# LightBox_Schematic_Updated_11-27.net
KiCad netlist of a schematic drawn in EAGLE
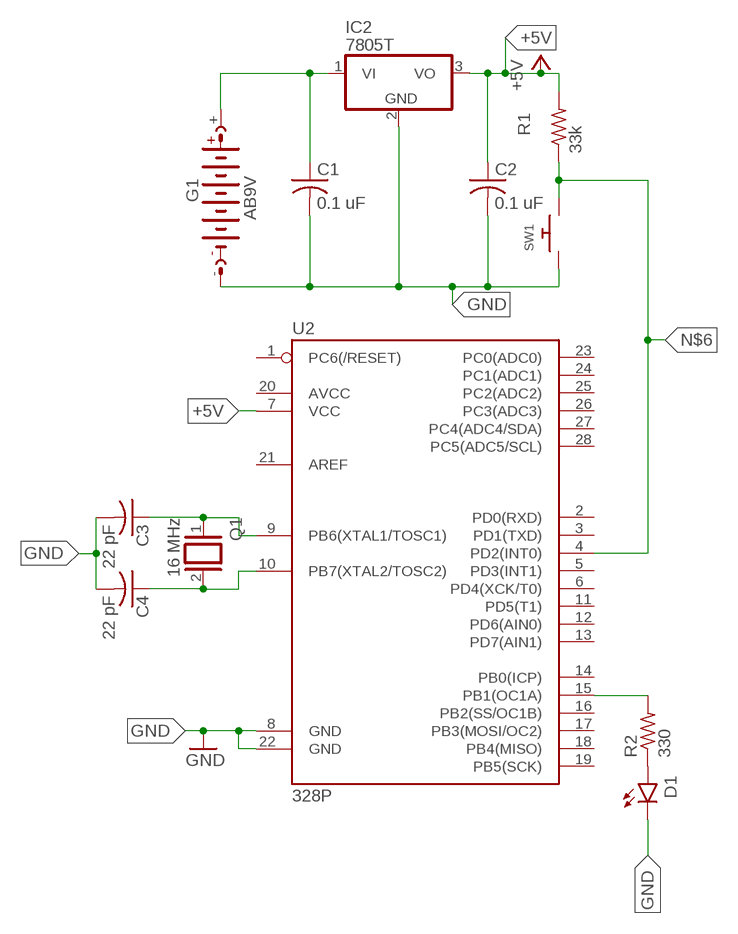
[diagram p0: schematic, sheet 1]

(export (version "E")
  (design (tool "Eeschema 10.0.6"))
  (components
    (comp (ref "C1")
      (value "0.1 uF")
      (footprint "eagle-import:C0805")
      (libsource (lib "eagle-import") (part "C-USC0805"))
    )
    (comp (ref "C2")
      (value "0.1 uF")
      (footprint "eagle-import:C0805")
      (libsource (lib "eagle-import") (part "C-USC0805"))
    )
    (comp (ref "C3")
      (value "22 pF")
      (footprint "eagle-import:C0805")
      (libsource (lib "eagle-import") (part "C-USC0805"))
    )
    (comp (ref "C4")
      (value "22 pF")
      (footprint "eagle-import:C0805")
      (libsource (lib "eagle-import") (part "C-USC0805"))
    )
    (comp (ref "D1")
      (value "LED3MM")
      (footprint "eagle-import:LED_3MM")
      (libsource (lib "eagle-import") (part "LED3MM"))
    )
    (comp (ref "G1")
      (value "AB9V")
      (footprint "eagle-import:AB9V")
      (libsource (lib "eagle-import") (part "AB9V"))
    )
    (comp (ref "IC2")
      (value "7805T")
      (footprint "eagle-import:TO220H")
      (libsource (lib "eagle-import") (part "78T05"))
    )
    (comp (ref "Q1")
      (value "16 MHz")
      (footprint "eagle-import:QS")
      (libsource (lib "eagle-import") (part "XTAL/S"))
    )
    (comp (ref "R1")
      (value "33k")
      (footprint "eagle-import:R0805")
      (libsource (lib "eagle-import") (part "R-US_R0805"))
    )
    (comp (ref "R2")
      (value "330")
      (footprint "eagle-import:R0805")
      (libsource (lib "eagle-import") (part "R-US_R0805"))
    )
    (comp (ref "SW1")
      (value "SWITCH_PUSHBUTTONEVQ-PE")
      (footprint "eagle-import:TACT_PANA-EVQ")
      (libsource (lib "eagle-import") (part "SWITCH_PUSHBUTTONEVQ-PE"))
    )
    (comp (ref "U2")
      (value "328P")
      (footprint "eagle-import:DIP28")
      (libsource (lib "eagle-import") (part "ATMEGA328P_PDIP"))
    )
  )
  (nets
    (net (code "1") (name "+5V") (class "Default")
      (node (ref "C2") (pin "1") (pinfunction "1_1") (pintype "passive"))
      (node (ref "IC2") (pin "3") (pinfunction "VO_3") (pintype "passive"))
      (node (ref "R1") (pin "2") (pinfunction "2_2") (pintype "passive"))
      (node (ref "U2") (pin "7") (pinfunction "VCC_7") (pintype "bidirectional"))
    )
    (net (code "2") (name "GND") (class "Default")
      (node (ref "C1") (pin "2") (pinfunction "2_2") (pintype "passive"))
      (node (ref "C2") (pin "2") (pinfunction "2_2") (pintype "passive"))
      (node (ref "C3") (pin "2") (pinfunction "2_2") (pintype "passive"))
      (node (ref "C4") (pin "2") (pinfunction "2_2") (pintype "passive"))
      (node (ref "D1") (pin "K") (pinfunction "C_K") (pintype "passive"))
      (node (ref "G1") (pin "-") (pinfunction "-_-") (pintype "passive"))
      (node (ref "IC2") (pin "2") (pinfunction "GND_2") (pintype "passive"))
      (node (ref "SW1") (pin "P$1") (pinfunction "P$1_P$1") (pintype "passive"))
      (node (ref "U2") (pin "22") (pinfunction "GND_22") (pintype "bidirectional"))
      (node (ref "U2") (pin "8") (pinfunction "GND_8") (pintype "bidirectional"))
    )
    (net (code "3") (name "N$6") (class "Default")
      (node (ref "R1") (pin "1") (pinfunction "1_1") (pintype "passive"))
      (node (ref "SW1") (pin "P$2") (pinfunction "P$2_P$2") (pintype "passive"))
      (node (ref "U2") (pin "4") (pinfunction "PD2(INT0)_4") (pintype "bidirectional"))
    )
    (net (code "4") (name "Net-(D1-PadA)") (class "Default")
      (node (ref "D1") (pin "A") (pinfunction "A_A") (pintype "passive"))
      (node (ref "R2") (pin "1") (pinfunction "1_1") (pintype "passive"))
    )
    (net (code "5") (name "Net-(IC2-VI)") (class "Default")
      (node (ref "C1") (pin "1") (pinfunction "1_1") (pintype "passive"))
      (node (ref "G1") (pin "+") (pinfunction "+_+") (pintype "passive"))
      (node (ref "IC2") (pin "1") (pinfunction "VI_1") (pintype "input"))
    )
    (net (code "6") (name "Net-(U2-PB1(OC1A))") (class "Default")
      (node (ref "R2") (pin "2") (pinfunction "2_2") (pintype "passive"))
      (node (ref "U2") (pin "15") (pinfunction "PB1(OC1A)_15") (pintype "bidirectional"))
    )
    (net (code "7") (name "Net-(U2-PB6(XTAL1{slash}TOSC1))") (class "Default")
      (node (ref "C3") (pin "1") (pinfunction "1_1") (pintype "passive"))
      (node (ref "Q1") (pin "1") (pinfunction "1_1") (pintype "passive"))
      (node (ref "U2") (pin "9") (pinfunction "PB6(XTAL1/TOSC1)_9") (pintype "bidirectional"))
    )
    (net (code "8") (name "Net-(U2-PB7(XTAL2{slash}TOSC2))") (class "Default")
      (node (ref "C4") (pin "1") (pinfunction "1_1") (pintype "passive"))
      (node (ref "Q1") (pin "2") (pinfunction "2_2") (pintype "passive"))
      (node (ref "U2") (pin "10") (pinfunction "PB7(XTAL2/TOSC2)_10") (pintype "bidirectional"))
    )
    (net (code "9") (name "unconnected-(U2-AREF-Pad21)") (class "Default")
      (node (ref "U2") (pin "21") (pinfunction "AREF_21") (pintype "bidirectional"))
    )
    (net (code "10") (name "unconnected-(U2-AVCC-Pad20)") (class "Default")
      (node (ref "U2") (pin "20") (pinfunction "AVCC_20") (pintype "bidirectional"))
    )
    (net (code "11") (name "unconnected-(U2-PB0(ICP)-Pad14)") (class "Default")
      (node (ref "U2") (pin "14") (pinfunction "PB0(ICP)_14") (pintype "bidirectional"))
    )
    (net (code "12") (name "unconnected-(U2-PB2(SS{slash}OC1B)-Pad16)") (class "Default")
      (node (ref "U2") (pin "16") (pinfunction "PB2(SS/OC1B)_16") (pintype "bidirectional"))
    )
    (net (code "13") (name "unconnected-(U2-PB3(MOSI{slash}OC2)-Pad17)") (class "Default")
      (node (ref "U2") (pin "17") (pinfunction "PB3(MOSI/OC2)_17") (pintype "bidirectional"))
    )
    (net (code "14") (name "unconnected-(U2-PB4(MISO)-Pad18)") (class "Default")
      (node (ref "U2") (pin "18") (pinfunction "PB4(MISO)_18") (pintype "bidirectional"))
    )
    (net (code "15") (name "unconnected-(U2-PB5(SCK)-Pad19)") (class "Default")
      (node (ref "U2") (pin "19") (pinfunction "PB5(SCK)_19") (pintype "bidirectional"))
    )
    (net (code "16") (name "unconnected-(U2-PC0(ADC0)-Pad23)") (class "Default")
      (node (ref "U2") (pin "23") (pinfunction "PC0(ADC0)_23") (pintype "bidirectional"))
    )
    (net (code "17") (name "unconnected-(U2-PC1(ADC1)-Pad24)") (class "Default")
      (node (ref "U2") (pin "24") (pinfunction "PC1(ADC1)_24") (pintype "bidirectional"))
    )
    (net (code "18") (name "unconnected-(U2-PC2(ADC2)-Pad25)") (class "Default")
      (node (ref "U2") (pin "25") (pinfunction "PC2(ADC2)_25") (pintype "bidirectional"))
    )
    (net (code "19") (name "unconnected-(U2-PC3(ADC3)-Pad26)") (class "Default")
      (node (ref "U2") (pin "26") (pinfunction "PC3(ADC3)_26") (pintype "bidirectional"))
    )
    (net (code "20") (name "unconnected-(U2-PC4(ADC4{slash}SDA)-Pad27)") (class "Default")
      (node (ref "U2") (pin "27") (pinfunction "PC4(ADC4/SDA)_27") (pintype "bidirectional"))
    )
    (net (code "21") (name "unconnected-(U2-PC5(ADC5{slash}SCL)-Pad28)") (class "Default")
      (node (ref "U2") (pin "28") (pinfunction "PC5(ADC5/SCL)_28") (pintype "bidirectional"))
    )
    (net (code "22") (name "unconnected-(U2-PC6({slash}RESET)-Pad1)") (class "Default")
      (node (ref "U2") (pin "1") (pinfunction "PC6(/RESET)_1") (pintype "bidirectional"))
    )
    (net (code "23") (name "unconnected-(U2-PD0(RXD)-Pad2)") (class "Default")
      (node (ref "U2") (pin "2") (pinfunction "PD0(RXD)_2") (pintype "bidirectional"))
    )
    (net (code "24") (name "unconnected-(U2-PD1(TXD)-Pad3)") (class "Default")
      (node (ref "U2") (pin "3") (pinfunction "PD1(TXD)_3") (pintype "bidirectional"))
    )
    (net (code "25") (name "unconnected-(U2-PD3(INT1)-Pad5)") (class "Default")
      (node (ref "U2") (pin "5") (pinfunction "PD3(INT1)_5") (pintype "bidirectional"))
    )
    (net (code "26") (name "unconnected-(U2-PD4(XCK{slash}T0)-Pad6)") (class "Default")
      (node (ref "U2") (pin "6") (pinfunction "PD4(XCK/T0)_6") (pintype "bidirectional"))
    )
    (net (code "27") (name "unconnected-(U2-PD5(T1)-Pad11)") (class "Default")
      (node (ref "U2") (pin "11") (pinfunction "PD5(T1)_11") (pintype "bidirectional"))
    )
    (net (code "28") (name "unconnected-(U2-PD6(AIN0)-Pad12)") (class "Default")
      (node (ref "U2") (pin "12") (pinfunction "PD6(AIN0)_12") (pintype "bidirectional"))
    )
    (net (code "29") (name "unconnected-(U2-PD7(AIN1)-Pad13)") (class "Default")
      (node (ref "U2") (pin "13") (pinfunction "PD7(AIN1)_13") (pintype "bidirectional"))
    )
  )
)
